# Peripherals.net
KiCad netlist of a schematic drawn in Altium Designer
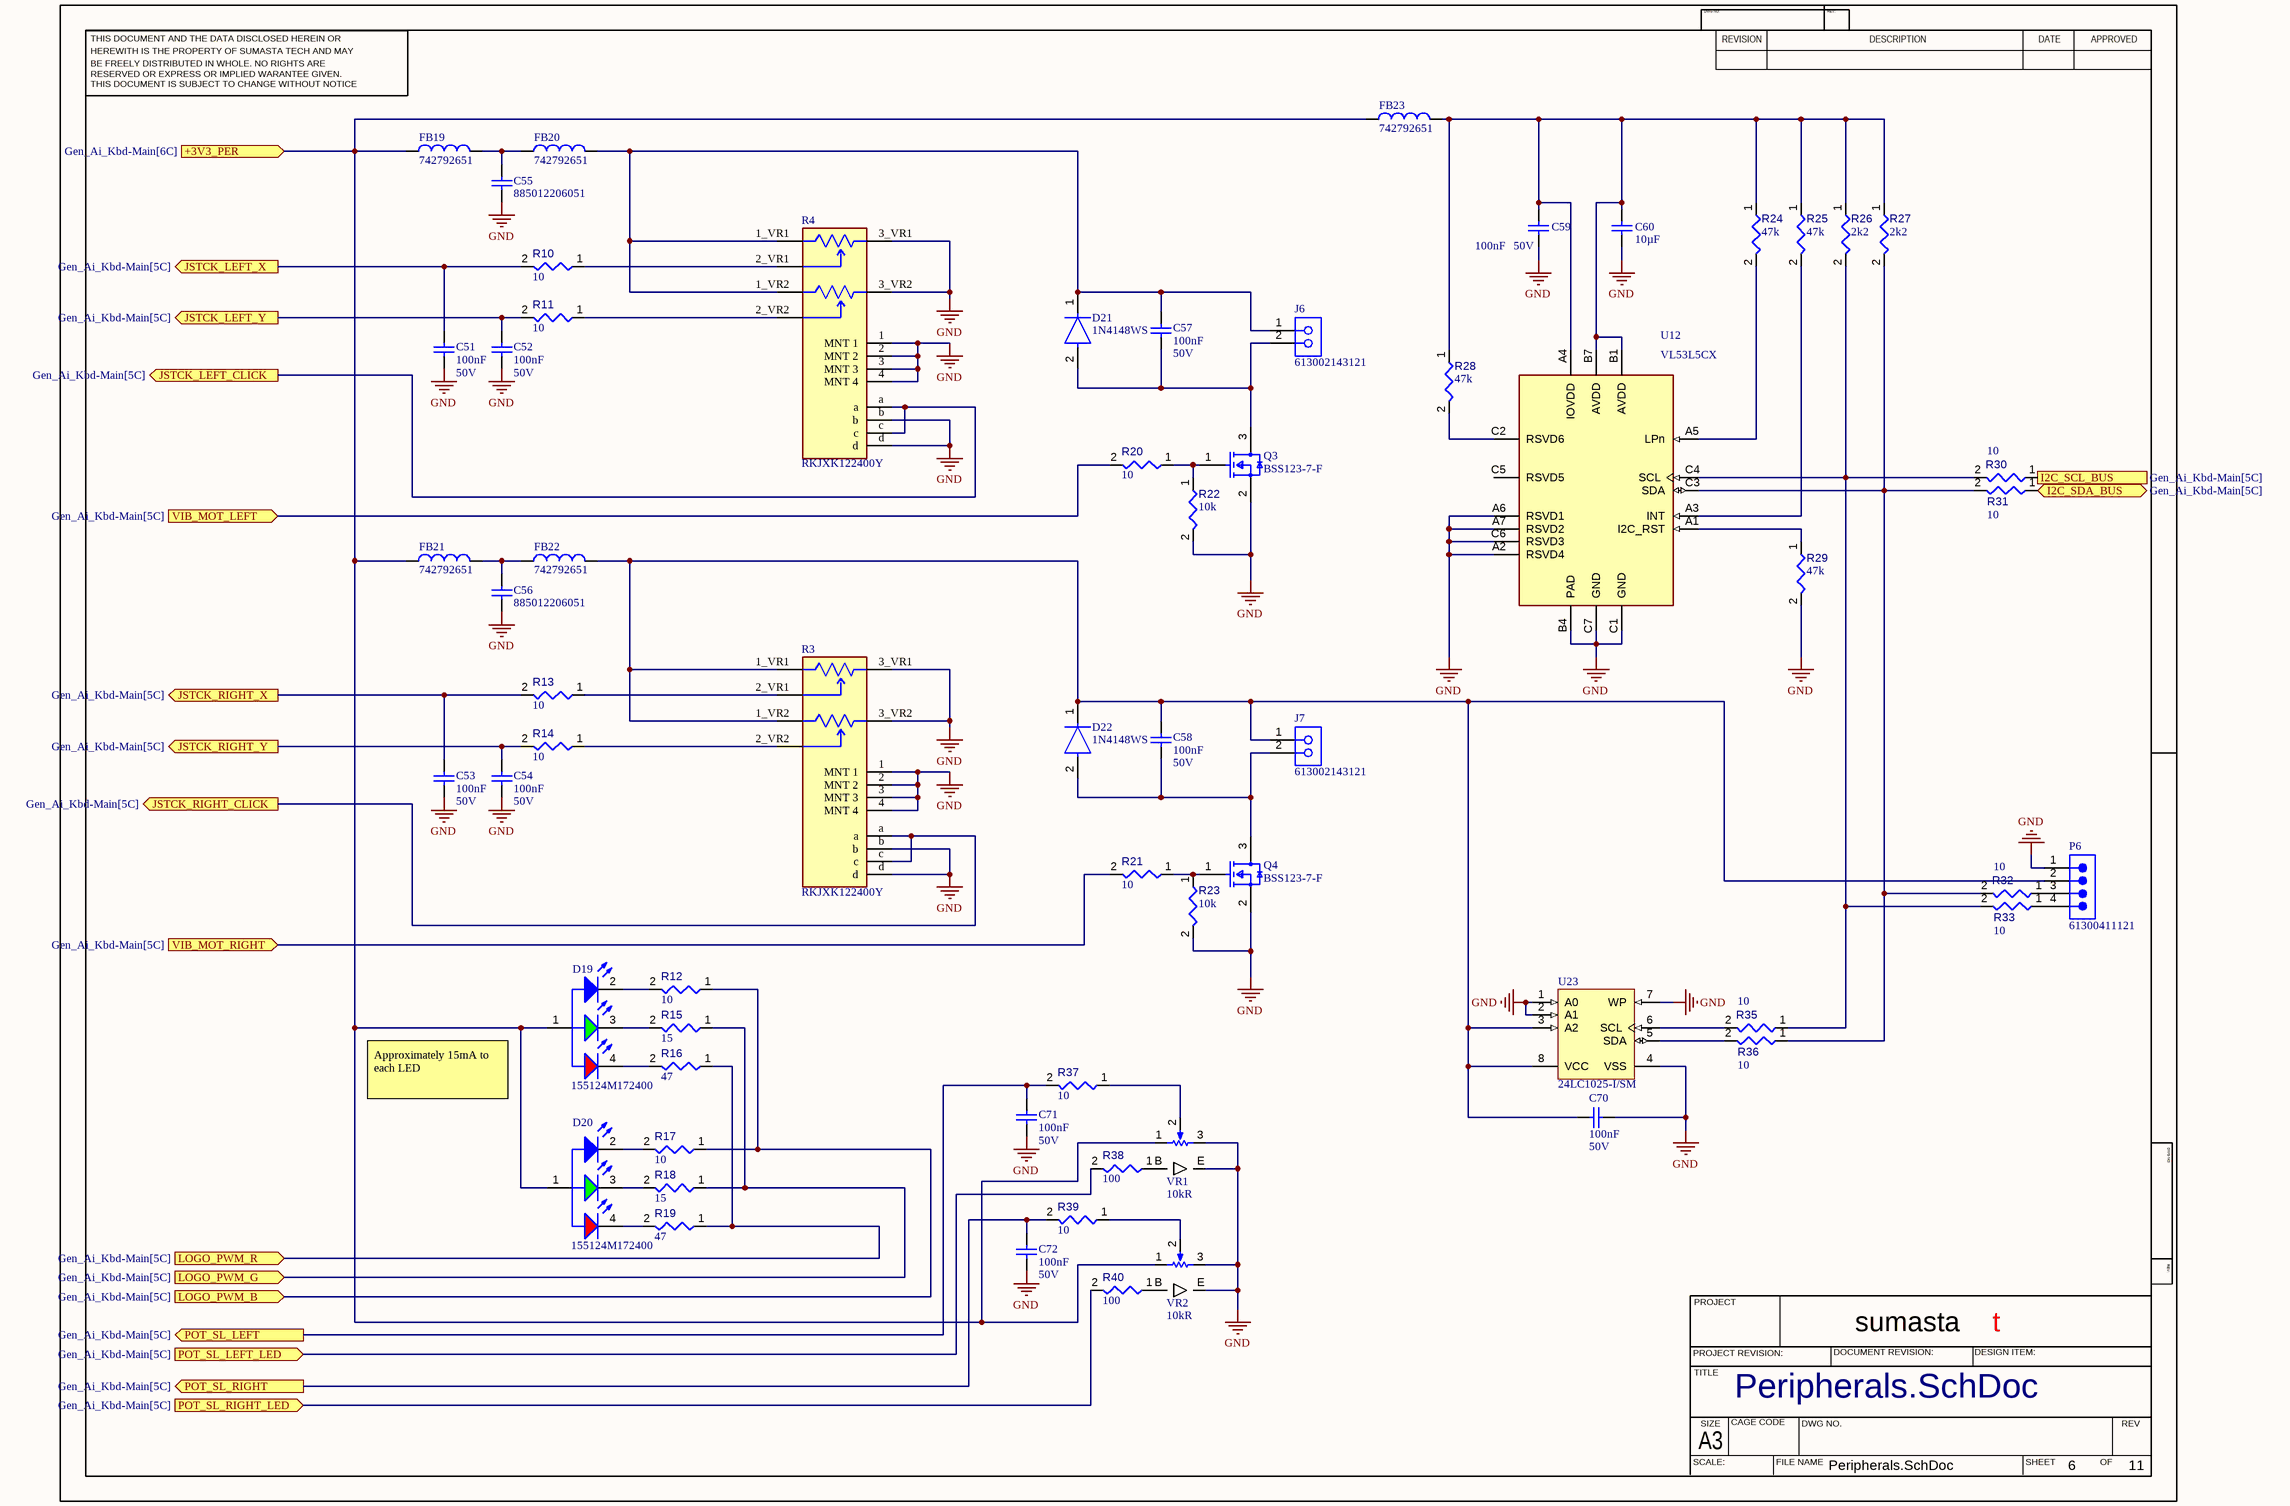
[diagram p0: Peripherals.SchDoc]

(export (version "E")
  (design (tool "Eeschema 10.0.6"))
  (components
    (comp (ref "C51")
      (value "885012206095")
      (footprint "WCAP-CSGP_0603_L1.6W0.8H0.8_Reflow")
      (description "WCAP-CSGP Multilayer Ceramic Chip Capacitor, General Purpose, size 0603, X7R, 100nF, 50VDC")
      (fields
        (field (name "CAPACITANCE") "100nF")
        (field (name "MANUFACTURER") "Wurth Elektronik")
        (field (name "RATED VOLTAGE (DC)") "50V")
      )
      (libsource (lib "Test365") (part "885012209047R"))
    )
    (comp (ref "C52")
      (value "885012206095")
      (footprint "WCAP-CSGP_0603_L1.6W0.8H0.8_Reflow")
      (description "WCAP-CSGP Multilayer Ceramic Chip Capacitor, General Purpose, size 0603, X7R, 100nF, 50VDC")
      (fields
        (field (name "CAPACITANCE") "100nF")
        (field (name "MANUFACTURER") "Wurth Elektronik")
        (field (name "RATED VOLTAGE (DC)") "50V")
      )
      (libsource (lib "Test365") (part "885012209047R"))
    )
    (comp (ref "C53")
      (value "885012206095")
      (footprint "WCAP-CSGP_0603_L1.6W0.8H0.8_Reflow")
      (description "WCAP-CSGP Multilayer Ceramic Chip Capacitor, General Purpose, size 0603, X7R, 100nF, 50VDC")
      (fields
        (field (name "CAPACITANCE") "100nF")
        (field (name "MANUFACTURER") "Wurth Elektronik")
        (field (name "RATED VOLTAGE (DC)") "50V")
      )
      (libsource (lib "Test365") (part "885012209047R"))
    )
    (comp (ref "C54")
      (value "885012206095")
      (footprint "WCAP-CSGP_0603_L1.6W0.8H0.8_Reflow")
      (description "WCAP-CSGP Multilayer Ceramic Chip Capacitor, General Purpose, size 0603, X7R, 100nF, 50VDC")
      (fields
        (field (name "CAPACITANCE") "100nF")
        (field (name "MANUFACTURER") "Wurth Elektronik")
        (field (name "RATED VOLTAGE (DC)") "50V")
      )
      (libsource (lib "Test365") (part "885012209047R"))
    )
    (comp (ref "C55")
      (value "885012206051")
      (footprint "WCAP-CSGP_0603_L1.6W0.8H0.8_Reflow")
      (description "885012206051 Cap Cer 0.68UF 16V X7R 0603")
      (fields (field (name "TOLERANCE") "10%"))
      (libsource (lib "Altium Content Vault") (part "Capacitor_Non-Polarized"))
    )
    (comp (ref "C56")
      (value "885012206051")
      (footprint "WCAP-CSGP_0603_L1.6W0.8H0.8_Reflow")
      (description "885012206051 Cap Cer 0.68UF 16V X7R 0603")
      (fields (field (name "TOLERANCE") "10%"))
      (libsource (lib "Altium Content Vault") (part "Capacitor_Non-Polarized"))
    )
    (comp (ref "C57")
      (value "885012206095")
      (footprint "WCAP-CSGP_0603_L1.6W0.8H0.8_Reflow")
      (description "WCAP-CSGP Multilayer Ceramic Chip Capacitor, General Purpose, size 0603, X7R, 100nF, 50VDC")
      (fields
        (field (name "CAPACITANCE") "100nF")
        (field (name "MANUFACTURER") "Wurth Elektronik")
        (field (name "RATED VOLTAGE (DC)") "50V")
      )
      (libsource (lib "Test365") (part "885012209047R"))
    )
    (comp (ref "C58")
      (value "885012206095")
      (footprint "WCAP-CSGP_0603_L1.6W0.8H0.8_Reflow")
      (description "WCAP-CSGP Multilayer Ceramic Chip Capacitor, General Purpose, size 0603, X7R, 100nF, 50VDC")
      (fields
        (field (name "CAPACITANCE") "100nF")
        (field (name "MANUFACTURER") "Wurth Elektronik")
        (field (name "RATED VOLTAGE (DC)") "50V")
      )
      (libsource (lib "Test365") (part "885012209047R"))
    )
    (comp (ref "C59")
      (value "885012206095")
      (footprint "WCAP-CSGP_0603_L1.6W0.8H0.8_Reflow")
      (description "WCAP-CSGP Multilayer Ceramic Chip Capacitor, General Purpose, size 0603, X7R, 100nF, 50VDC")
      (fields
        (field (name "CAPACITANCE") "100nF")
        (field (name "MANUFACTURER") "Wurth Elektronik")
        (field (name "RATED VOLTAGE (DC)") "50V")
      )
      (libsource (lib "Test365") (part "885012209047R"))
    )
    (comp (ref "C60")
      (value "885012106006")
      (footprint "WCAP-CSGP_0603_L1.6W0.8H0.8_Reflow")
      (description "WCAP-CSGP Multilayer Ceramic Chip Capacitor, General Purpose, size 0603, X5R, 10µF, 6.3VDC")
      (fields (field (name "MANUFACTURER") "Wurth Elektronik") (field (name "CAPACITANCE") "10µF"))
      (libsource (lib "Test365") (part "885012209047R"))
    )
    (comp (ref "C70")
      (value "885012206095")
      (footprint "WCAP-CSGP_0603_L1.6W0.8H0.8_Reflow")
      (description "WCAP-CSGP Multilayer Ceramic Chip Capacitor, General Purpose, size 0603, X7R, 100nF, 50VDC")
      (fields
        (field (name "CAPACITANCE") "100nF")
        (field (name "MANUFACTURER") "Wurth Elektronik")
        (field (name "RATED VOLTAGE (DC)") "50V")
      )
      (libsource (lib "Test365") (part "885012209047R"))
    )
    (comp (ref "C71")
      (value "885012206095")
      (footprint "WCAP-CSGP_0603_L1.6W0.8H0.8_Reflow")
      (description "WCAP-CSGP Multilayer Ceramic Chip Capacitor, General Purpose, size 0603, X7R, 100nF, 50VDC")
      (fields
        (field (name "CAPACITANCE") "100nF")
        (field (name "MANUFACTURER") "Wurth Elektronik")
        (field (name "RATED VOLTAGE (DC)") "50V")
      )
      (libsource (lib "Test365") (part "885012209047R"))
    )
    (comp (ref "C72")
      (value "885012206095")
      (footprint "WCAP-CSGP_0603_L1.6W0.8H0.8_Reflow")
      (description "WCAP-CSGP Multilayer Ceramic Chip Capacitor, General Purpose, size 0603, X7R, 100nF, 50VDC")
      (fields
        (field (name "CAPACITANCE") "100nF")
        (field (name "MANUFACTURER") "Wurth Elektronik")
        (field (name "RATED VOLTAGE (DC)") "50V")
      )
      (libsource (lib "Test365") (part "885012209047R"))
    )
    (comp (ref "D19")
      (value "155124M172400")
      (footprint "WL-SFSW_1204_155124M172400")
      (description "155124M172400 Wl-sfsw SMT Full-color Side View")
      (libsource (lib "Altium Content Vault") (part "WL-SFSW_155124M172400"))
    )
    (comp (ref "D20")
      (value "155124M172400")
      (footprint "WL-SFSW_1204_155124M172400")
      (description "155124M172400 Wl-sfsw SMT Full-color Side View")
      (libsource (lib "Altium Content Vault") (part "WL-SFSW_155124M172400"))
    )
    (comp (ref "D21")
      (value "1N4148WS")
      (footprint "FP-477AB-IPC_C")
      (description "DIODE GEN PURP 75V 150MA SOD323F")
      (libsource (lib "Altium Content Vault") (part "d7152d700b627762746794eb795d46e"))
    )
    (comp (ref "D22")
      (value "1N4148WS")
      (footprint "FP-477AB-IPC_C")
      (description "DIODE GEN PURP 75V 150MA SOD323F")
      (libsource (lib "Altium Content Vault") (part "d7152d700b627762746794eb795d46e"))
    )
    (comp (ref "FB19")
      (value "742792651")
      (footprint "WE-CBF_0603_L1.6W0.8H0.8_HC")
      (fields (field (name "TOLERANCE") "25%"))
      (libsource (lib "Altium Content Vault") (part "Ferrite"))
    )
    (comp (ref "FB20")
      (value "742792651")
      (footprint "WE-CBF_0603_L1.6W0.8H0.8_HC")
      (fields (field (name "TOLERANCE") "25%"))
      (libsource (lib "Altium Content Vault") (part "Ferrite"))
    )
    (comp (ref "FB21")
      (value "742792651")
      (footprint "WE-CBF_0603_L1.6W0.8H0.8_HC")
      (fields (field (name "TOLERANCE") "25%"))
      (libsource (lib "Altium Content Vault") (part "Ferrite"))
    )
    (comp (ref "FB22")
      (value "742792651")
      (footprint "WE-CBF_0603_L1.6W0.8H0.8_HC")
      (fields (field (name "TOLERANCE") "25%"))
      (libsource (lib "Altium Content Vault") (part "Ferrite"))
    )
    (comp (ref "FB23")
      (value "742792651")
      (footprint "WE-CBF_0603_L1.6W0.8H0.8_HC")
      (fields (field (name "TOLERANCE") "25%"))
      (libsource (lib "Altium Content Vault") (part "Ferrite"))
    )
    (comp (ref "J6")
      (value "613002143121")
      (footprint "613002143121")
      (libsource (lib "Altium Content Vault") (part "Header_Female_1R_02P"))
    )
    (comp (ref "J7")
      (value "613002143121")
      (footprint "613002143121")
      (libsource (lib "Altium Content Vault") (part "Header_Female_1R_02P"))
    )
    (comp (ref "P6")
      (value "61300411121")
      (footprint "61300411121")
      (libsource (lib "Altium Content Vault") (part "Header_Male_1R_04P"))
    )
    (comp (ref "Q3")
      (value "BSS123-7-F")
      (footprint "FP-SOT23-MFG")
      (description "MOSFET N-CH 100V 170MA SOT23-3")
      (fields
        (field (name "OCTOPART") "https://octopart.com/bss123-7-f-diodes+inc.-335886")
        (field (name "MANUFACTURER") "Diodes Incorporated")
      )
      (libsource (lib "Altium Content Vault") (part "1661867509f36a4ffa577829538a895"))
    )
    (comp (ref "Q4")
      (value "BSS123-7-F")
      (footprint "FP-SOT23-MFG")
      (description "MOSFET N-CH 100V 170MA SOT23-3")
      (fields
        (field (name "OCTOPART") "https://octopart.com/bss123-7-f-diodes+inc.-335886")
        (field (name "MANUFACTURER") "Diodes Incorporated")
      )
      (libsource (lib "Altium Content Vault") (part "1661867509f36a4ffa577829538a895"))
    )
    (comp (ref "R3")
      (value "RKJXK122400Y")
      (footprint "FP-RKJXK122400Y-MFG")
      (description "Res POT 10K Ohm 0.0125W (25.4 X 20.7 X 19.3mm) Pin Bracket Mount/Through Hole Tray")
      (libsource (lib "Altium Content Vault") (part "63a56dd8e99e1e1552a3870b2e96c5c"))
    )
    (comp (ref "R4")
      (value "RKJXK122400Y")
      (footprint "FP-RKJXK122400Y-MFG")
      (description "Res POT 10K Ohm 0.0125W (25.4 X 20.7 X 19.3mm) Pin Bracket Mount/Through Hole Tray")
      (libsource (lib "Altium Content Vault") (part "63a56dd8e99e1e1552a3870b2e96c5c"))
    )
    (comp (ref "R10")
      (value "10")
      (footprint "RESC1608X55X25ML10T15")
      (description "Chip Resistor, 10 KOhm, +/- 1%, 01 W, -55 to 155 degC, 0603 (1608 Metric)")
      (fields (field (name "POWER") "100mW") (field (name "TOLERANCE") "1%"))
      (libsource (lib "Test365") (part "RES-2"))
    )
    (comp (ref "R11")
      (value "10")
      (footprint "RESC1608X55X25ML10T15")
      (description "Chip Resistor, 10 KOhm, +/- 1%, 01 W, -55 to 155 degC, 0603 (1608 Metric)")
      (fields (field (name "POWER") "100mW") (field (name "TOLERANCE") "1%"))
      (libsource (lib "Test365") (part "RES-2"))
    )
    (comp (ref "R12")
      (value "10")
      (footprint "RESC1608X55X25ML10T15")
      (description "Chip Resistor, 10 KOhm, +/- 1%, 01 W, -55 to 155 degC, 0603 (1608 Metric)")
      (fields (field (name "POWER") "100mW") (field (name "TOLERANCE") "1%"))
      (libsource (lib "Test365") (part "RES-2"))
    )
    (comp (ref "R13")
      (value "10")
      (footprint "RESC1608X55X25ML10T15")
      (description "Chip Resistor, 10 KOhm, +/- 1%, 01 W, -55 to 155 degC, 0603 (1608 Metric)")
      (fields (field (name "POWER") "100mW") (field (name "TOLERANCE") "1%"))
      (libsource (lib "Test365") (part "RES-2"))
    )
    (comp (ref "R14")
      (value "10")
      (footprint "RESC1608X55X25ML10T15")
      (description "Chip Resistor, 10 KOhm, +/- 1%, 01 W, -55 to 155 degC, 0603 (1608 Metric)")
      (fields (field (name "POWER") "100mW") (field (name "TOLERANCE") "1%"))
      (libsource (lib "Test365") (part "RES-2"))
    )
    (comp (ref "R15")
      (value "15")
      (footprint "RESC1608X55X25ML10T15")
      (description "Chip Resistor, 10 KOhm, +/- 1%, 01 W, -55 to 155 degC, 0603 (1608 Metric)")
      (fields (field (name "POWER") "100mW") (field (name "TOLERANCE") "1%"))
      (libsource (lib "Test365") (part "RES-2"))
    )
    (comp (ref "R16")
      (value "47")
      (footprint "RESC1608X55X25ML10T15")
      (description "Chip Resistor, 10 KOhm, +/- 1%, 01 W, -55 to 155 degC, 0603 (1608 Metric)")
      (fields (field (name "POWER") "100mW") (field (name "TOLERANCE") "1%"))
      (libsource (lib "Test365") (part "RES-2"))
    )
    (comp (ref "R17")
      (value "10")
      (footprint "RESC1608X55X25ML10T15")
      (description "Chip Resistor, 10 KOhm, +/- 1%, 01 W, -55 to 155 degC, 0603 (1608 Metric)")
      (fields (field (name "POWER") "100mW") (field (name "TOLERANCE") "1%"))
      (libsource (lib "Test365") (part "RES-2"))
    )
    (comp (ref "R18")
      (value "15")
      (footprint "RESC1608X55X25ML10T15")
      (description "Chip Resistor, 10 KOhm, +/- 1%, 01 W, -55 to 155 degC, 0603 (1608 Metric)")
      (fields (field (name "POWER") "100mW") (field (name "TOLERANCE") "1%"))
      (libsource (lib "Test365") (part "RES-2"))
    )
    (comp (ref "R19")
      (value "47")
      (footprint "RESC1608X55X25ML10T15")
      (description "Chip Resistor, 10 KOhm, +/- 1%, 01 W, -55 to 155 degC, 0603 (1608 Metric)")
      (fields (field (name "POWER") "100mW") (field (name "TOLERANCE") "1%"))
      (libsource (lib "Test365") (part "RES-2"))
    )
    (comp (ref "R20")
      (value "10")
      (footprint "RESC1608X55X25ML10T15")
      (description "Chip Resistor, 10 KOhm, +/- 1%, 01 W, -55 to 155 degC, 0603 (1608 Metric)")
      (fields (field (name "POWER") "100mW") (field (name "TOLERANCE") "1%"))
      (libsource (lib "Test365") (part "RES-2"))
    )
    (comp (ref "R21")
      (value "10")
      (footprint "RESC1608X55X25ML10T15")
      (description "Chip Resistor, 10 KOhm, +/- 1%, 01 W, -55 to 155 degC, 0603 (1608 Metric)")
      (fields (field (name "POWER") "100mW") (field (name "TOLERANCE") "1%"))
      (libsource (lib "Test365") (part "RES-2"))
    )
    (comp (ref "R22")
      (value "10k")
      (footprint "RESC1608X55X25ML10T15")
      (description "Chip Resistor, 10 KOhm, +/- 1%, 01 W, -55 to 155 degC, 0603 (1608 Metric)")
      (fields (field (name "POWER") "100mW") (field (name "TOLERANCE") "1%"))
      (libsource (lib "Test365") (part "RES-2"))
    )
    (comp (ref "R23")
      (value "10k")
      (footprint "RESC1608X55X25ML10T15")
      (description "Chip Resistor, 10 KOhm, +/- 1%, 01 W, -55 to 155 degC, 0603 (1608 Metric)")
      (fields (field (name "POWER") "100mW") (field (name "TOLERANCE") "1%"))
      (libsource (lib "Test365") (part "RES-2"))
    )
    (comp (ref "R24")
      (value "47k")
      (footprint "RESC1608X55X25ML10T15")
      (description "Chip Resistor, 10 KOhm, +/- 1%, 01 W, -55 to 155 degC, 0603 (1608 Metric)")
      (fields (field (name "POWER") "100mW") (field (name "TOLERANCE") "1%"))
      (libsource (lib "Test365") (part "RES-2"))
    )
    (comp (ref "R25")
      (value "47k")
      (footprint "RESC1608X55X25ML10T15")
      (description "Chip Resistor, 10 KOhm, +/- 1%, 01 W, -55 to 155 degC, 0603 (1608 Metric)")
      (fields (field (name "POWER") "100mW") (field (name "TOLERANCE") "1%"))
      (libsource (lib "Test365") (part "RES-2"))
    )
    (comp (ref "R26")
      (value "2k2")
      (footprint "RESC1608X55X25ML10T15")
      (description "Chip Resistor, 10 KOhm, +/- 1%, 01 W, -55 to 155 degC, 0603 (1608 Metric)")
      (fields (field (name "POWER") "100mW") (field (name "TOLERANCE") "1%"))
      (libsource (lib "Test365") (part "RES-2"))
    )
    (comp (ref "R27")
      (value "2k2")
      (footprint "RESC1608X55X25ML10T15")
      (description "Chip Resistor, 10 KOhm, +/- 1%, 01 W, -55 to 155 degC, 0603 (1608 Metric)")
      (fields (field (name "POWER") "100mW") (field (name "TOLERANCE") "1%"))
      (libsource (lib "Test365") (part "RES-2"))
    )
    (comp (ref "R28")
      (value "47k")
      (footprint "RESC1608X55X25ML10T15")
      (description "Chip Resistor, 10 KOhm, +/- 1%, 01 W, -55 to 155 degC, 0603 (1608 Metric)")
      (fields (field (name "POWER") "100mW") (field (name "TOLERANCE") "1%"))
      (libsource (lib "Test365") (part "RES-2"))
    )
    (comp (ref "R29")
      (value "47k")
      (footprint "RESC1608X55X25ML10T15")
      (description "Chip Resistor, 10 KOhm, +/- 1%, 01 W, -55 to 155 degC, 0603 (1608 Metric)")
      (fields (field (name "POWER") "100mW") (field (name "TOLERANCE") "1%"))
      (libsource (lib "Test365") (part "RES-2"))
    )
    (comp (ref "R30")
      (value "10")
      (footprint "RESC1608X55X25ML10T15")
      (description "Chip Resistor, 10 KOhm, +/- 1%, 01 W, -55 to 155 degC, 0603 (1608 Metric)")
      (fields (field (name "POWER") "100mW") (field (name "TOLERANCE") "1%"))
      (libsource (lib "Test365") (part "RES-2"))
    )
    (comp (ref "R31")
      (value "10")
      (footprint "RESC1608X55X25ML10T15")
      (description "Chip Resistor, 10 KOhm, +/- 1%, 01 W, -55 to 155 degC, 0603 (1608 Metric)")
      (fields (field (name "POWER") "100mW") (field (name "TOLERANCE") "1%"))
      (libsource (lib "Test365") (part "RES-2"))
    )
    (comp (ref "R32")
      (value "10")
      (footprint "RESC1608X55X25ML10T15")
      (description "Chip Resistor, 10 KOhm, +/- 1%, 01 W, -55 to 155 degC, 0603 (1608 Metric)")
      (fields (field (name "POWER") "100mW") (field (name "TOLERANCE") "1%"))
      (libsource (lib "Test365") (part "RES-2"))
    )
    (comp (ref "R33")
      (value "10")
      (footprint "RESC1608X55X25ML10T15")
      (description "Chip Resistor, 10 KOhm, +/- 1%, 01 W, -55 to 155 degC, 0603 (1608 Metric)")
      (fields (field (name "POWER") "100mW") (field (name "TOLERANCE") "1%"))
      (libsource (lib "Test365") (part "RES-2"))
    )
    (comp (ref "R35")
      (value "10")
      (footprint "RESC1608X55X25ML10T15")
      (description "Chip Resistor, 10 KOhm, +/- 1%, 01 W, -55 to 155 degC, 0603 (1608 Metric)")
      (fields (field (name "POWER") "100mW") (field (name "TOLERANCE") "1%"))
      (libsource (lib "Test365") (part "RES-2"))
    )
    (comp (ref "R36")
      (value "10")
      (footprint "RESC1608X55X25ML10T15")
      (description "Chip Resistor, 10 KOhm, +/- 1%, 01 W, -55 to 155 degC, 0603 (1608 Metric)")
      (fields (field (name "POWER") "100mW") (field (name "TOLERANCE") "1%"))
      (libsource (lib "Test365") (part "RES-2"))
    )
    (comp (ref "R37")
      (value "10")
      (footprint "RESC1608X55X25ML10T15")
      (description "Chip Resistor, 10 KOhm, +/- 1%, 01 W, -55 to 155 degC, 0603 (1608 Metric)")
      (fields (field (name "POWER") "100mW") (field (name "TOLERANCE") "1%"))
      (libsource (lib "Test365") (part "RES-2"))
    )
    (comp (ref "R38")
      (value "100")
      (footprint "RESC1608X55X25ML10T15")
      (description "Chip Resistor, 10 KOhm, +/- 1%, 01 W, -55 to 155 degC, 0603 (1608 Metric)")
      (fields (field (name "POWER") "100mW") (field (name "TOLERANCE") "1%"))
      (libsource (lib "Test365") (part "RES-2"))
    )
    (comp (ref "R39")
      (value "10")
      (footprint "RESC1608X55X25ML10T15")
      (description "Chip Resistor, 10 KOhm, +/- 1%, 01 W, -55 to 155 degC, 0603 (1608 Metric)")
      (fields (field (name "POWER") "100mW") (field (name "TOLERANCE") "1%"))
      (libsource (lib "Test365") (part "RES-2"))
    )
    (comp (ref "R40")
      (value "100")
      (footprint "RESC1608X55X25ML10T15")
      (description "Chip Resistor, 10 KOhm, +/- 1%, 01 W, -55 to 155 degC, 0603 (1608 Metric)")
      (fields (field (name "POWER") "100mW") (field (name "TOLERANCE") "1%"))
      (libsource (lib "Test365") (part "RES-2"))
    )
    (comp (ref "U12")
      (value "VL53L5CX")
      (footprint "VL53L5CX")
      (description "VL53L5CX - 8X8 Segment, Light, 3D Time-of-Flight _ToF_ Sensor Evaluation Board")
      (libsource (lib "Test365") (part "VL53L5CX"))
    )
    (comp (ref "U23")
      (value "24LC1025-I/SM")
      (footprint "SOIJ-SM8_L")
      (description "1 Mbit, 400kHz, 2.5V, I2C Serial EEPROM, 8-Pin SOIC 208mil, Industrial Temperature")
      (libsource (lib "Altium Content Vault") (part "MEM-SEEPROM-34AA02-IL8"))
    )
    (comp (ref "VR1")
      (value "10kR")
      (footprint "PTL30-15R0")
      (fields
        (field (name "TOLERANCE") "20%")
        (field (name "MANUFACTURER") "Bourns")
        (field (name "POWER") "500mW")
      )
      (libsource (lib "Test365") (part "RES-POT-3-LED"))
    )
    (comp (ref "VR2")
      (value "10kR")
      (footprint "PTL30-15R0")
      (fields
        (field (name "TOLERANCE") "20%")
        (field (name "MANUFACTURER") "Bourns")
        (field (name "POWER") "500mW")
      )
      (libsource (lib "Test365") (part "RES-POT-3-LED"))
    )
  )
  (nets
    (net (code "1") (name "/+3V3_PER") (class "Default")
      (node (ref "D19") (pin "1") (pinfunction "A_1") (pintype "passive"))
      (node (ref "D20") (pin "1") (pinfunction "A_1") (pintype "passive"))
      (node (ref "FB19") (pin "1") (pinfunction "1_1") (pintype "passive"))
      (node (ref "FB21") (pin "1") (pinfunction "1_1") (pintype "passive"))
      (node (ref "FB23") (pin "1") (pinfunction "1_1") (pintype "passive"))
      (node (ref "VR1") (pin "1") (pinfunction "CW_1") (pintype "passive"))
      (node (ref "VR2") (pin "1") (pinfunction "CW_1") (pintype "passive"))
    )
    (net (code "2") (name "/I2C_SCL_BUS") (class "Default")
      (node (ref "R30") (pin "1") (pinfunction "1_1") (pintype "passive"))
    )
    (net (code "3") (name "/I2C_SDA_BUS") (class "Default")
      (node (ref "R31") (pin "1") (pinfunction "1_1") (pintype "passive"))
    )
    (net (code "4") (name "/JSTCK_LEFT_CLICK") (class "Default")
      (node (ref "R4") (pin "a") (pinfunction "a_a") (pintype "passive"))
      (node (ref "R4") (pin "c") (pinfunction "c_c") (pintype "passive"))
    )
    (net (code "5") (name "/JSTCK_LEFT_X") (class "Default")
      (node (ref "C51") (pin "1") (pinfunction "1_1") (pintype "passive"))
      (node (ref "R10") (pin "2") (pinfunction "2_2") (pintype "passive"))
    )
    (net (code "6") (name "/JSTCK_LEFT_Y") (class "Default")
      (node (ref "C52") (pin "1") (pinfunction "1_1") (pintype "passive"))
      (node (ref "R11") (pin "2") (pinfunction "2_2") (pintype "passive"))
    )
    (net (code "7") (name "/JSTCK_RIGHT_CLICK") (class "Default")
      (node (ref "R3") (pin "a") (pinfunction "a_a") (pintype "passive"))
      (node (ref "R3") (pin "c") (pinfunction "c_c") (pintype "passive"))
    )
    (net (code "8") (name "/JSTCK_RIGHT_X") (class "Default")
      (node (ref "C53") (pin "1") (pinfunction "1_1") (pintype "passive"))
      (node (ref "R13") (pin "2") (pinfunction "2_2") (pintype "passive"))
    )
    (net (code "9") (name "/JSTCK_RIGHT_Y") (class "Default")
      (node (ref "C54") (pin "1") (pinfunction "1_1") (pintype "passive"))
      (node (ref "R14") (pin "2") (pinfunction "2_2") (pintype "passive"))
    )
    (net (code "10") (name "/LOGO_PWM_B") (class "Default")
      (node (ref "R12") (pin "1") (pinfunction "1_1") (pintype "passive"))
      (node (ref "R17") (pin "1") (pinfunction "1_1") (pintype "passive"))
    )
    (net (code "11") (name "/LOGO_PWM_G") (class "Default")
      (node (ref "R15") (pin "1") (pinfunction "1_1") (pintype "passive"))
      (node (ref "R18") (pin "1") (pinfunction "1_1") (pintype "passive"))
    )
    (net (code "12") (name "/LOGO_PWM_R") (class "Default")
      (node (ref "R16") (pin "1") (pinfunction "1_1") (pintype "passive"))
      (node (ref "R19") (pin "1") (pinfunction "1_1") (pintype "passive"))
    )
    (net (code "13") (name "/POT_SL_LEFT") (class "Default")
      (node (ref "C71") (pin "1") (pinfunction "1_1") (pintype "passive"))
      (node (ref "R37") (pin "2") (pinfunction "2_2") (pintype "passive"))
    )
    (net (code "14") (name "/POT_SL_LEFT_LED") (class "Default")
      (node (ref "R38") (pin "2") (pinfunction "2_2") (pintype "passive"))
    )
    (net (code "15") (name "/POT_SL_RIGHT") (class "Default")
      (node (ref "C72") (pin "1") (pinfunction "1_1") (pintype "passive"))
      (node (ref "R39") (pin "2") (pinfunction "2_2") (pintype "passive"))
    )
    (net (code "16") (name "/POT_SL_RIGHT_LED") (class "Default")
      (node (ref "R40") (pin "2") (pinfunction "2_2") (pintype "passive"))
    )
    (net (code "17") (name "/VIB_MOT_LEFT") (class "Default")
      (node (ref "R20") (pin "2") (pinfunction "2_2") (pintype "passive"))
    )
    (net (code "18") (name "/VIB_MOT_RIGHT") (class "Default")
      (node (ref "R21") (pin "2") (pinfunction "2_2") (pintype "passive"))
    )
    (net (code "19") (name "GND") (class "Default")
      (node (ref "C51") (pin "2") (pinfunction "2_2") (pintype "passive"))
      (node (ref "C52") (pin "2") (pinfunction "2_2") (pintype "passive"))
      (node (ref "C53") (pin "2") (pinfunction "2_2") (pintype "passive"))
      (node (ref "C54") (pin "2") (pinfunction "2_2") (pintype "passive"))
      (node (ref "C55") (pin "1") (pinfunction "1_1") (pintype "passive"))
      (node (ref "C56") (pin "1") (pinfunction "1_1") (pintype "passive"))
      (node (ref "C59") (pin "1") (pinfunction "1_1") (pintype "passive"))
      (node (ref "C60") (pin "1") (pinfunction "1_1") (pintype "passive"))
      (node (ref "C70") (pin "1") (pinfunction "1_1") (pintype "passive"))
      (node (ref "C71") (pin "2") (pinfunction "2_2") (pintype "passive"))
      (node (ref "C72") (pin "2") (pinfunction "2_2") (pintype "passive"))
      (node (ref "P6") (pin "1") (pinfunction "1_1") (pintype "passive"))
      (node (ref "Q3") (pin "2") (pinfunction "S_2") (pintype "passive"))
      (node (ref "Q4") (pin "2") (pinfunction "S_2") (pintype "passive"))
      (node (ref "R22") (pin "2") (pinfunction "2_2") (pintype "passive"))
      (node (ref "R23") (pin "2") (pinfunction "2_2") (pintype "passive"))
      (node (ref "R29") (pin "2") (pinfunction "2_2") (pintype "passive"))
      (node (ref "R3") (pin "1") (pinfunction "MNT_1_1") (pintype "passive"))
      (node (ref "R3") (pin "2") (pinfunction "MNT_2_2") (pintype "passive"))
      (node (ref "R3") (pin "3") (pinfunction "MNT_3_3") (pintype "passive"))
      (node (ref "R3") (pin "3_VR1") (pinfunction "3_VR1_3_VR1") (pintype "passive"))
      (node (ref "R3") (pin "3_VR2") (pinfunction "3_VR2_3_VR2") (pintype "passive"))
      (node (ref "R3") (pin "4") (pinfunction "MNT_4_4") (pintype "passive"))
      (node (ref "R3") (pin "b") (pinfunction "b_b") (pintype "passive"))
      (node (ref "R3") (pin "d") (pinfunction "d_d") (pintype "passive"))
      (node (ref "R4") (pin "1") (pinfunction "MNT_1_1") (pintype "passive"))
      (node (ref "R4") (pin "2") (pinfunction "MNT_2_2") (pintype "passive"))
      (node (ref "R4") (pin "3") (pinfunction "MNT_3_3") (pintype "passive"))
      (node (ref "R4") (pin "3_VR1") (pinfunction "3_VR1_3_VR1") (pintype "passive"))
      (node (ref "R4") (pin "3_VR2") (pinfunction "3_VR2_3_VR2") (pintype "passive"))
      (node (ref "R4") (pin "4") (pinfunction "MNT_4_4") (pintype "passive"))
      (node (ref "R4") (pin "b") (pinfunction "b_b") (pintype "passive"))
      (node (ref "R4") (pin "d") (pinfunction "d_d") (pintype "passive"))
      (node (ref "U12") (pin "A2") (pinfunction "RSVD4_A2") (pintype "passive"))
      (node (ref "U12") (pin "A6") (pinfunction "RSVD1_A6") (pintype "passive"))
      (node (ref "U12") (pin "A7") (pinfunction "RSVD2_A7") (pintype "passive"))
      (node (ref "U12") (pin "B4") (pinfunction "PAD_B4") (pintype "power_in"))
      (node (ref "U12") (pin "C1") (pinfunction "GND_C1") (pintype "power_in"))
      (node (ref "U12") (pin "C6") (pinfunction "RSVD3_C6") (pintype "passive"))
      (node (ref "U12") (pin "C7") (pinfunction "GND_C7") (pintype "power_in"))
      (node (ref "U23") (pin "1") (pinfunction "A0_1") (pintype "input"))
      (node (ref "U23") (pin "2") (pinfunction "A1_2") (pintype "input"))
      (node (ref "U23") (pin "4") (pinfunction "VSS_4") (pintype "power_in"))
      (node (ref "U23") (pin "7") (pinfunction "WP_7") (pintype "input"))
      (node (ref "VR1") (pin "3") (pinfunction "CCW_3") (pintype "passive"))
      (node (ref "VR1") (pin "E") (pinfunction "CCW_E") (pintype "passive"))
      (node (ref "VR2") (pin "3") (pinfunction "CCW_3") (pintype "passive"))
      (node (ref "VR2") (pin "E") (pinfunction "CCW_E") (pintype "passive"))
    )
    (net (code "20") (name "Net-(C55-Pad2)") (class "Default")
      (node (ref "C55") (pin "2") (pinfunction "2_2") (pintype "passive"))
      (node (ref "FB19") (pin "2") (pinfunction "2_2") (pintype "passive"))
      (node (ref "FB20") (pin "1") (pinfunction "1_1") (pintype "passive"))
    )
    (net (code "21") (name "Net-(C56-Pad2)") (class "Default")
      (node (ref "C56") (pin "2") (pinfunction "2_2") (pintype "passive"))
      (node (ref "FB21") (pin "2") (pinfunction "2_2") (pintype "passive"))
      (node (ref "FB22") (pin "1") (pinfunction "1_1") (pintype "passive"))
    )
    (net (code "22") (name "Net-(D19-K-Pad2)") (class "Default")
      (node (ref "D19") (pin "2") (pinfunction "K_2") (pintype "passive"))
      (node (ref "R12") (pin "2") (pinfunction "2_2") (pintype "passive"))
    )
    (net (code "23") (name "Net-(D19-K-Pad3)") (class "Default")
      (node (ref "D19") (pin "3") (pinfunction "K_3") (pintype "passive"))
      (node (ref "R15") (pin "2") (pinfunction "2_2") (pintype "passive"))
    )
    (net (code "24") (name "Net-(D19-K-Pad4)") (class "Default")
      (node (ref "D19") (pin "4") (pinfunction "K_4") (pintype "passive"))
      (node (ref "R16") (pin "2") (pinfunction "2_2") (pintype "passive"))
    )
    (net (code "25") (name "Net-(D20-K-Pad2)") (class "Default")
      (node (ref "D20") (pin "2") (pinfunction "K_2") (pintype "passive"))
      (node (ref "R17") (pin "2") (pinfunction "2_2") (pintype "passive"))
    )
    (net (code "26") (name "Net-(D20-K-Pad3)") (class "Default")
      (node (ref "D20") (pin "3") (pinfunction "K_3") (pintype "passive"))
      (node (ref "R18") (pin "2") (pinfunction "2_2") (pintype "passive"))
    )
    (net (code "27") (name "Net-(D20-K-Pad4)") (class "Default")
      (node (ref "D20") (pin "4") (pinfunction "K_4") (pintype "passive"))
      (node (ref "R19") (pin "2") (pinfunction "2_2") (pintype "passive"))
    )
    (net (code "28") (name "Net-(D21-A)") (class "Default")
      (node (ref "C57") (pin "2") (pinfunction "2_2") (pintype "passive"))
      (node (ref "D21") (pin "2") (pinfunction "A_2") (pintype "passive"))
      (node (ref "J6") (pin "2") (pinfunction "2_2") (pintype "passive"))
      (node (ref "Q3") (pin "3") (pinfunction "D_3") (pintype "passive"))
    )
    (net (code "29") (name "Net-(D21-C)") (class "Default")
      (node (ref "C57") (pin "1") (pinfunction "1_1") (pintype "passive"))
      (node (ref "D21") (pin "1") (pinfunction "C_1") (pintype "passive"))
      (node (ref "FB20") (pin "2") (pinfunction "2_2") (pintype "passive"))
      (node (ref "J6") (pin "1") (pinfunction "1_1") (pintype "passive"))
      (node (ref "R4") (pin "1_VR1") (pinfunction "1_VR1_1_VR1") (pintype "passive"))
      (node (ref "R4") (pin "1_VR2") (pinfunction "1_VR2_1_VR2") (pintype "passive"))
    )
    (net (code "30") (name "Net-(D22-A)") (class "Default")
      (node (ref "C58") (pin "2") (pinfunction "2_2") (pintype "passive"))
      (node (ref "D22") (pin "2") (pinfunction "A_2") (pintype "passive"))
      (node (ref "J7") (pin "2") (pinfunction "2_2") (pintype "passive"))
      (node (ref "Q4") (pin "3") (pinfunction "D_3") (pintype "passive"))
    )
    (net (code "31") (name "Net-(D22-C)") (class "Default")
      (node (ref "C58") (pin "1") (pinfunction "1_1") (pintype "passive"))
      (node (ref "C70") (pin "2") (pinfunction "2_2") (pintype "passive"))
      (node (ref "D22") (pin "1") (pinfunction "C_1") (pintype "passive"))
      (node (ref "FB22") (pin "2") (pinfunction "2_2") (pintype "passive"))
      (node (ref "J7") (pin "1") (pinfunction "1_1") (pintype "passive"))
      (node (ref "P6") (pin "2") (pinfunction "2_2") (pintype "passive"))
      (node (ref "R3") (pin "1_VR1") (pinfunction "1_VR1_1_VR1") (pintype "passive"))
      (node (ref "R3") (pin "1_VR2") (pinfunction "1_VR2_1_VR2") (pintype "passive"))
      (node (ref "U23") (pin "3") (pinfunction "A2_3") (pintype "input"))
      (node (ref "U23") (pin "8") (pinfunction "VCC_8") (pintype "power_in"))
    )
    (net (code "32") (name "Net-(P6-Pad3)") (class "Default")
      (node (ref "P6") (pin "3") (pinfunction "3_3") (pintype "passive"))
      (node (ref "R32") (pin "1") (pinfunction "1_1") (pintype "passive"))
    )
    (net (code "33") (name "Net-(P6-Pad4)") (class "Default")
      (node (ref "P6") (pin "4") (pinfunction "4_4") (pintype "passive"))
      (node (ref "R33") (pin "1") (pinfunction "1_1") (pintype "passive"))
    )
    (net (code "34") (name "Net-(Q3-G)") (class "Default")
      (node (ref "Q3") (pin "1") (pinfunction "G_1") (pintype "passive"))
      (node (ref "R20") (pin "1") (pinfunction "1_1") (pintype "passive"))
      (node (ref "R22") (pin "1") (pinfunction "1_1") (pintype "passive"))
    )
    (net (code "35") (name "Net-(Q4-G)") (class "Default")
      (node (ref "Q4") (pin "1") (pinfunction "G_1") (pintype "passive"))
      (node (ref "R21") (pin "1") (pinfunction "1_1") (pintype "passive"))
      (node (ref "R23") (pin "1") (pinfunction "1_1") (pintype "passive"))
    )
    (net (code "36") (name "Net-(R10-Pad1)") (class "Default")
      (node (ref "R10") (pin "1") (pinfunction "1_1") (pintype "passive"))
      (node (ref "R4") (pin "2_VR1") (pinfunction "2_VR1_2_VR1") (pintype "passive"))
    )
    (net (code "37") (name "Net-(R11-Pad1)") (class "Default")
      (node (ref "R11") (pin "1") (pinfunction "1_1") (pintype "passive"))
      (node (ref "R4") (pin "2_VR2") (pinfunction "2_VR2_2_VR2") (pintype "passive"))
    )
    (net (code "38") (name "Net-(R13-Pad1)") (class "Default")
      (node (ref "R13") (pin "1") (pinfunction "1_1") (pintype "passive"))
      (node (ref "R3") (pin "2_VR1") (pinfunction "2_VR1_2_VR1") (pintype "passive"))
    )
    (net (code "39") (name "Net-(R14-Pad1)") (class "Default")
      (node (ref "R14") (pin "1") (pinfunction "1_1") (pintype "passive"))
      (node (ref "R3") (pin "2_VR2") (pinfunction "2_VR2_2_VR2") (pintype "passive"))
    )
    (net (code "40") (name "Net-(R38-Pad1)") (class "Default")
      (node (ref "R38") (pin "1") (pinfunction "1_1") (pintype "passive"))
      (node (ref "VR1") (pin "B") (pinfunction "CCW_B") (pintype "passive"))
    )
    (net (code "41") (name "Net-(R40-Pad1)") (class "Default")
      (node (ref "R40") (pin "1") (pinfunction "1_1") (pintype "passive"))
      (node (ref "VR2") (pin "B") (pinfunction "CCW_B") (pintype "passive"))
    )
    (net (code "42") (name "Net-(U12-I2C_RST)") (class "Default")
      (node (ref "R29") (pin "1") (pinfunction "1_1") (pintype "passive"))
      (node (ref "U12") (pin "A1") (pinfunction "I2C_RST_A1") (pintype "input"))
    )
    (net (code "43") (name "Net-(U12-INT)") (class "Default")
      (node (ref "R25") (pin "2") (pinfunction "2_2") (pintype "passive"))
      (node (ref "U12") (pin "A3") (pinfunction "INT_A3") (pintype "input"))
    )
    (net (code "44") (name "Net-(U12-IOVDD)") (class "Default")
      (node (ref "C59") (pin "2") (pinfunction "2_2") (pintype "passive"))
      (node (ref "C60") (pin "2") (pinfunction "2_2") (pintype "passive"))
      (node (ref "FB23") (pin "2") (pinfunction "2_2") (pintype "passive"))
      (node (ref "R24") (pin "1") (pinfunction "1_1") (pintype "passive"))
      (node (ref "R25") (pin "1") (pinfunction "1_1") (pintype "passive"))
      (node (ref "R26") (pin "1") (pinfunction "1_1") (pintype "passive"))
      (node (ref "R27") (pin "1") (pinfunction "1_1") (pintype "passive"))
      (node (ref "R28") (pin "1") (pinfunction "1_1") (pintype "passive"))
      (node (ref "U12") (pin "A4") (pinfunction "IOVDD_A4") (pintype "power_in"))
      (node (ref "U12") (pin "B1") (pinfunction "AVDD_B1") (pintype "power_in"))
      (node (ref "U12") (pin "B7") (pinfunction "AVDD_B7") (pintype "power_in"))
    )
    (net (code "45") (name "Net-(U12-LPn)") (class "Default")
      (node (ref "R24") (pin "2") (pinfunction "2_2") (pintype "passive"))
      (node (ref "U12") (pin "A5") (pinfunction "LPn_A5") (pintype "input"))
    )
    (net (code "46") (name "Net-(U12-RSVD6)") (class "Default")
      (node (ref "R28") (pin "2") (pinfunction "2_2") (pintype "passive"))
      (node (ref "U12") (pin "C2") (pinfunction "RSVD6_C2") (pintype "passive"))
    )
    (net (code "47") (name "Net-(U12-SCL)") (class "Default")
      (node (ref "R26") (pin "2") (pinfunction "2_2") (pintype "passive"))
      (node (ref "R30") (pin "2") (pinfunction "2_2") (pintype "passive"))
      (node (ref "R33") (pin "2") (pinfunction "2_2") (pintype "passive"))
      (node (ref "R35") (pin "1") (pinfunction "1_1") (pintype "passive"))
      (node (ref "U12") (pin "C4") (pinfunction "SCL_C4") (pintype "input"))
    )
    (net (code "48") (name "Net-(U12-SDA)") (class "Default")
      (node (ref "R27") (pin "2") (pinfunction "2_2") (pintype "passive"))
      (node (ref "R31") (pin "2") (pinfunction "2_2") (pintype "passive"))
      (node (ref "R32") (pin "2") (pinfunction "2_2") (pintype "passive"))
      (node (ref "R36") (pin "1") (pinfunction "1_1") (pintype "passive"))
      (node (ref "U12") (pin "C3") (pinfunction "SDA_C3") (pintype "bidirectional"))
    )
    (net (code "49") (name "Net-(U23-SCL)") (class "Default")
      (node (ref "R35") (pin "2") (pinfunction "2_2") (pintype "passive"))
      (node (ref "U23") (pin "6") (pinfunction "SCL_6") (pintype "input"))
    )
    (net (code "50") (name "Net-(U23-SDA)") (class "Default")
      (node (ref "R36") (pin "2") (pinfunction "2_2") (pintype "passive"))
      (node (ref "U23") (pin "5") (pinfunction "SDA_5") (pintype "bidirectional"))
    )
    (net (code "51") (name "Net-(VR1-S)") (class "Default")
      (node (ref "R37") (pin "1") (pinfunction "1_1") (pintype "passive"))
      (node (ref "VR1") (pin "2") (pinfunction "S_2") (pintype "passive"))
    )
    (net (code "52") (name "Net-(VR2-S)") (class "Default")
      (node (ref "R39") (pin "1") (pinfunction "1_1") (pintype "passive"))
      (node (ref "VR2") (pin "2") (pinfunction "S_2") (pintype "passive"))
    )
    (net (code "53") (name "unconnected-(U12-RSVD5-PadC5)") (class "Default")
      (node (ref "U12") (pin "C5") (pinfunction "RSVD5_C5") (pintype "passive"))
    )
  )
)
